# motordriver-v5_0_isolation-general.net
KiCad netlist of a schematic drawn in Altium Designer
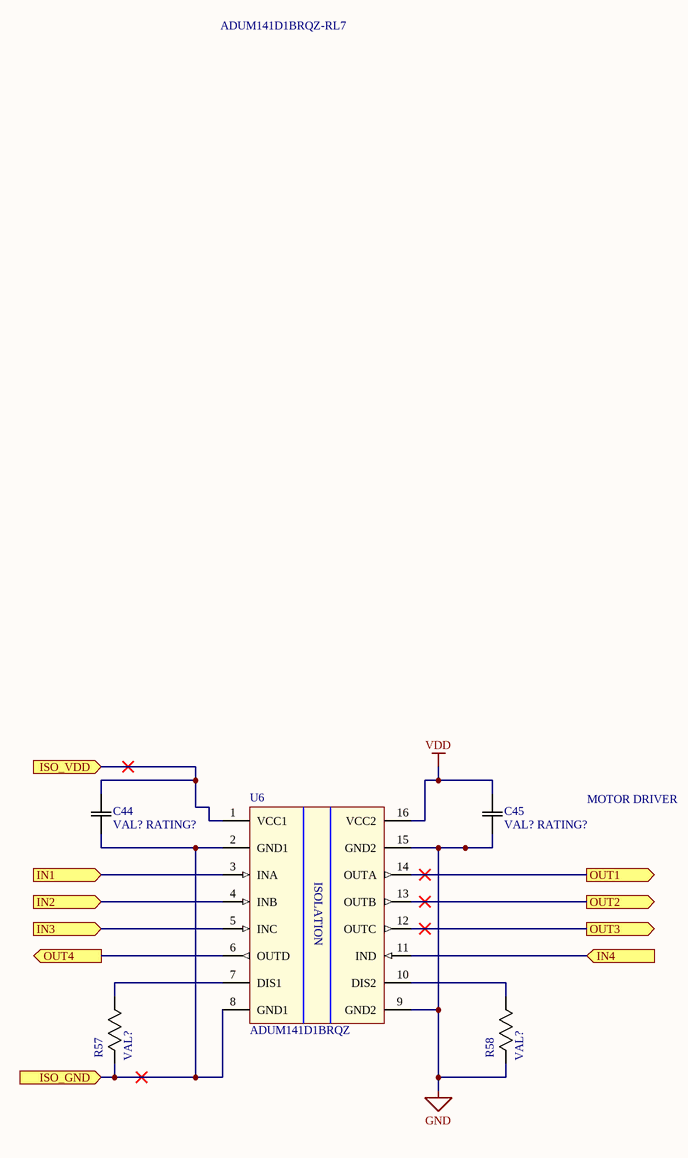
[diagram p0: motordriver-v5.0_isolation-general.SchDoc]

(export (version "E")
  (design (tool "Eeschema 10.0.6"))
  (components
    (comp (ref "C44")
      (value "VAL? RATING?")
      (footprint "0603")
      (description "Default Symbol for Capacitors")
      (fields (field (name "PART NUMBER") "CAP 100nF 50V") (field (name "TOLERANCE") "10%"))
      (libsource (lib "capacitor_library") (part "CAP_Default"))
    )
    (comp (ref "C45")
      (value "VAL? RATING?")
      (footprint "0603")
      (description "Default Symbol for Capacitors")
      (fields (field (name "PART NUMBER") "CAP 100nF 50V") (field (name "TOLERANCE") "10%"))
      (libsource (lib "capacitor_library") (part "CAP_Default"))
    )
    (comp (ref "R57")
      (value "VAL?")
      (footprint "0603")
      (description "Default Resistor Symbol")
      (fields (field (name "TOLERANCE") "5%") (field (name "PART NUMBER") "RES 4.7k 1/8W - 5%"))
      (libsource (lib "Resistor_Library") (part "RES_DEFAULT"))
    )
    (comp (ref "R58")
      (value "VAL?")
      (footprint "0603")
      (description "Default Resistor Symbol")
      (fields (field (name "TOLERANCE") "5%") (field (name "PART NUMBER") "RES 4.7k 1/8W - 5%"))
      (libsource (lib "Resistor_Library") (part "RES_DEFAULT"))
    )
    (comp (ref "U6")
      (value "ADUM141D1BRQZ")
      (footprint "SOP64P600X175-16N")
      (description "Digital Isolator CMOS 4-CH 150Mbps 16-Pin QSOP T/R")
      (fields
        (field (name "MANUFACTURER") "Analog Devices")
        (field (name "MANUFACTURER PART NUMBER") "ADUM141D1BRQZ-RL7")
        (field (name "SUPPLIER PART NUMBER 1") "ADUM141D1BRQZ-RL7")
      )
      (libsource (lib "AltiumLibraries") (part "ISO ADUM141D1BRQZ"))
    )
  )
  (nets
    (net (code "1") (name "/IN1") (class "Default")
      (node (ref "U6") (pin "3") (pinfunction "INA_3") (pintype "input"))
    )
    (net (code "2") (name "/IN2") (class "Default")
      (node (ref "U6") (pin "4") (pinfunction "INB_4") (pintype "input"))
    )
    (net (code "3") (name "/IN3") (class "Default")
      (node (ref "U6") (pin "5") (pinfunction "INC_5") (pintype "input"))
    )
    (net (code "4") (name "/IN4") (class "Default")
      (node (ref "U6") (pin "11") (pinfunction "IND_11") (pintype "input"))
    )
    (net (code "5") (name "/ISO_GND") (class "Default")
      (node (ref "C44") (pin "1") (pinfunction "C1_1") (pintype "passive"))
      (node (ref "R57") (pin "2") (pinfunction "R2_2") (pintype "passive"))
      (node (ref "U6") (pin "2") (pinfunction "GND1_2") (pintype "power_in"))
      (node (ref "U6") (pin "8") (pinfunction "GND1_8") (pintype "power_in"))
    )
    (net (code "6") (name "/ISO_VDD") (class "Default")
      (node (ref "C44") (pin "2") (pinfunction "C2_2") (pintype "passive"))
      (node (ref "U6") (pin "1") (pinfunction "VCC1_1") (pintype "power_in"))
    )
    (net (code "7") (name "/OUT1") (class "Default")
      (node (ref "U6") (pin "14") (pinfunction "OUTA_14") (pintype "output"))
    )
    (net (code "8") (name "/OUT2") (class "Default")
      (node (ref "U6") (pin "13") (pinfunction "OUTB_13") (pintype "output"))
    )
    (net (code "9") (name "/OUT3") (class "Default")
      (node (ref "U6") (pin "12") (pinfunction "OUTC_12") (pintype "output"))
    )
    (net (code "10") (name "/OUT4") (class "Default")
      (node (ref "U6") (pin "6") (pinfunction "OUTD_6") (pintype "output"))
    )
    (net (code "11") (name "GND") (class "Default")
      (node (ref "C45") (pin "1") (pinfunction "C1_1") (pintype "passive"))
      (node (ref "R58") (pin "2") (pinfunction "R2_2") (pintype "passive"))
      (node (ref "U6") (pin "15") (pinfunction "GND2_15") (pintype "power_in"))
      (node (ref "U6") (pin "9") (pinfunction "GND2_9") (pintype "power_in"))
    )
    (net (code "12") (name "Net-(R57-R1)") (class "Default")
      (node (ref "R57") (pin "1") (pinfunction "R1_1") (pintype "passive"))
      (node (ref "U6") (pin "7") (pinfunction "DIS1_7") (pintype "passive"))
    )
    (net (code "13") (name "Net-(R58-R1)") (class "Default")
      (node (ref "R58") (pin "1") (pinfunction "R1_1") (pintype "passive"))
      (node (ref "U6") (pin "10") (pinfunction "DIS2_10") (pintype "passive"))
    )
    (net (code "14") (name "VDD") (class "Default")
      (node (ref "C45") (pin "2") (pinfunction "C2_2") (pintype "passive"))
      (node (ref "U6") (pin "16") (pinfunction "VCC2_16") (pintype "power_in"))
    )
  )
)
